# motor_control.net
KiCad netlist of a schematic drawn in EAGLE
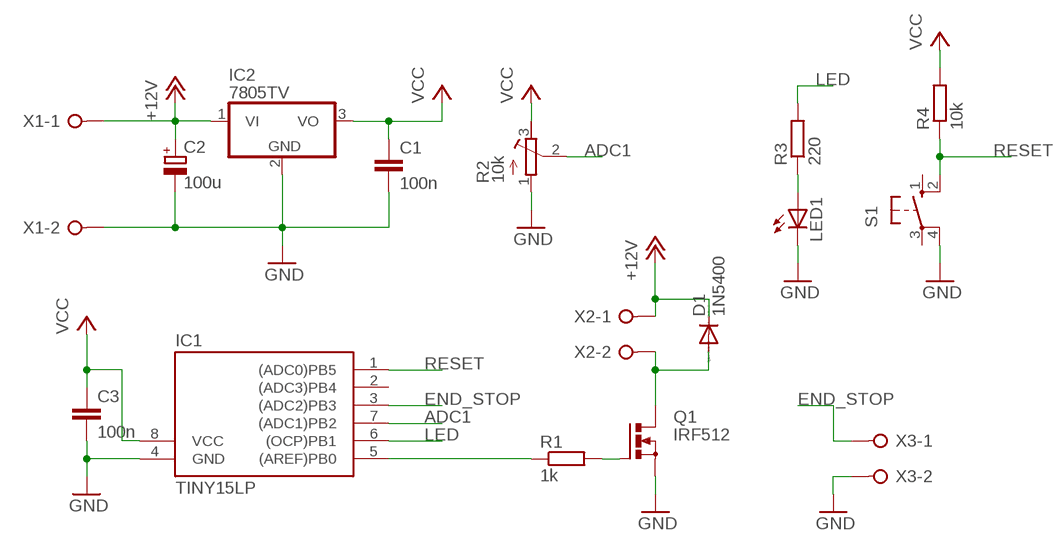
[diagram p0: schematic, sheet 1]

(export (version "E")
  (design (tool "Eeschema 10.0.6"))
  (components
    (comp (ref "C1")
      (value "100n")
      (footprint "eagle-import:C025-025X050")
      (libsource (lib "eagle-import") (part "C-EU025-025X050"))
    )
    (comp (ref "C2")
      (value "100u")
      (footprint "eagle-import:E2,5-6E")
      (libsource (lib "eagle-import") (part "CPOL-EUE2,5-6E"))
    )
    (comp (ref "C3")
      (value "100n")
      (footprint "eagle-import:C025-025X050")
      (libsource (lib "eagle-import") (part "C-EU025-025X050"))
    )
    (comp (ref "D1")
      (value "1N5400")
      (footprint "eagle-import:DO201-15")
      (libsource (lib "eagle-import") (part "1N5400"))
    )
    (comp (ref "IC1")
      (value "TINY15LP")
      (footprint "eagle-import:DIL08")
      (libsource (lib "eagle-import") (part "TINY15LP"))
    )
    (comp (ref "IC2")
      (value "7805TV")
      (footprint "eagle-import:TO220V")
      (libsource (lib "eagle-import") (part "78TV05"))
    )
    (comp (ref "LED1")
      (value "LED5MM")
      (footprint "eagle-import:LED5MM")
      (libsource (lib "eagle-import") (part "LED5MM"))
    )
    (comp (ref "Q1")
      (value "IRF512")
      (footprint "eagle-import:TO220BV")
      (libsource (lib "eagle-import") (part "IRF512"))
    )
    (comp (ref "R1")
      (value "1k")
      (footprint "eagle-import:0309_10")
      (libsource (lib "eagle-import") (part "R-EU_0309/10"))
    )
    (comp (ref "R2")
      (value "10k")
      (footprint "eagle-import:RTRIM3296W")
      (libsource (lib "eagle-import") (part "R-TRIMM3296W"))
    )
    (comp (ref "R3")
      (value "220")
      (footprint "eagle-import:0309_10")
      (libsource (lib "eagle-import") (part "R-EU_0309/10"))
    )
    (comp (ref "R4")
      (value "10k")
      (footprint "eagle-import:0309_10")
      (libsource (lib "eagle-import") (part "R-EU_0309/10"))
    )
    (comp (ref "S1")
      (value "40-XX")
      (footprint "eagle-import:B3F-40XX")
      (fields (field (name "MF") "OMRON COMPONENTS USA") (field (name "MPN") "B3F-4000"))
      (libsource (lib "eagle-import") (part "40-XX"))
    )
    (comp (ref "X1")
      (value "W237-02P")
      (footprint "eagle-import:W237-132")
      (libsource (lib "eagle-import") (part "W237-02P"))
    )
    (comp (ref "X2")
      (value "W237-02P")
      (footprint "eagle-import:W237-132")
      (libsource (lib "eagle-import") (part "W237-02P"))
    )
    (comp (ref "X3")
      (value "W237-02P")
      (footprint "eagle-import:W237-132")
      (libsource (lib "eagle-import") (part "W237-02P"))
    )
  )
  (nets
    (net (code "1") (name "+12V") (class "Default")
      (node (ref "C2") (pin "+") (pinfunction "+_+") (pintype "passive"))
      (node (ref "D1") (pin "C") (pinfunction "C_C") (pintype "passive"))
      (node (ref "IC2") (pin "1") (pinfunction "VI_1") (pintype "input"))
      (node (ref "X1") (pin "1") (pinfunction "KL_1") (pintype "passive"))
      (node (ref "X2") (pin "1") (pinfunction "KL_1") (pintype "passive"))
    )
    (net (code "2") (name "/ADC1") (class "Default")
      (node (ref "IC1") (pin "7") (pinfunction "(ADC1)PB2_7") (pintype "bidirectional"))
      (node (ref "R2") (pin "2") (pinfunction "S_2") (pintype "passive"))
    )
    (net (code "3") (name "/END_STOP") (class "Default")
      (node (ref "IC1") (pin "3") (pinfunction "(ADC2)PB3_3") (pintype "bidirectional"))
      (node (ref "X3") (pin "1") (pinfunction "KL_1") (pintype "passive"))
    )
    (net (code "4") (name "/LED") (class "Default")
      (node (ref "IC1") (pin "6") (pinfunction "(OCP)PB1_6") (pintype "bidirectional"))
      (node (ref "R3") (pin "2") (pinfunction "2_2") (pintype "passive"))
    )
    (net (code "5") (name "/RESET") (class "Default")
      (node (ref "IC1") (pin "1") (pinfunction "(ADC0)PB5_1") (pintype "bidirectional"))
      (node (ref "R4") (pin "1") (pinfunction "1_1") (pintype "passive"))
      (node (ref "S1") (pin "2") (pinfunction "S1_2") (pintype "passive"))
    )
    (net (code "6") (name "GND") (class "Default")
      (node (ref "C1") (pin "2") (pinfunction "2_2") (pintype "passive"))
      (node (ref "C2") (pin "-") (pinfunction "-_-") (pintype "passive"))
      (node (ref "C3") (pin "2") (pinfunction "2_2") (pintype "passive"))
      (node (ref "IC1") (pin "4") (pinfunction "GND_4") (pintype "power_in"))
      (node (ref "IC2") (pin "2") (pinfunction "GND_2") (pintype "passive"))
      (node (ref "LED1") (pin "K") (pinfunction "C_K") (pintype "passive"))
      (node (ref "Q1") (pin "S") (pinfunction "S_S") (pintype "passive"))
      (node (ref "R2") (pin "1") (pinfunction "A_1") (pintype "passive"))
      (node (ref "S1") (pin "4") (pinfunction "P1_4") (pintype "passive"))
      (node (ref "X1") (pin "2") (pinfunction "KL_2") (pintype "passive"))
      (node (ref "X3") (pin "2") (pinfunction "KL_2") (pintype "passive"))
    )
    (net (code "7") (name "Net-(IC1-(AREF)PB0)") (class "Default")
      (node (ref "IC1") (pin "5") (pinfunction "(AREF)PB0_5") (pintype "bidirectional"))
      (node (ref "R1") (pin "1") (pinfunction "1_1") (pintype "passive"))
    )
    (net (code "8") (name "Net-(LED1-PadA)") (class "Default")
      (node (ref "LED1") (pin "A") (pinfunction "A_A") (pintype "passive"))
      (node (ref "R3") (pin "1") (pinfunction "1_1") (pintype "passive"))
    )
    (net (code "9") (name "Net-(Q1-PadG)") (class "Default")
      (node (ref "Q1") (pin "G") (pinfunction "G_G") (pintype "passive"))
      (node (ref "R1") (pin "2") (pinfunction "2_2") (pintype "passive"))
    )
    (net (code "10") (name "Net-(X2B-KL)") (class "Default")
      (node (ref "D1") (pin "A") (pinfunction "A_A") (pintype "passive"))
      (node (ref "Q1") (pin "D") (pinfunction "D_D") (pintype "passive"))
      (node (ref "X2") (pin "2") (pinfunction "KL_2") (pintype "passive"))
    )
    (net (code "11") (name "VCC") (class "Default")
      (node (ref "C1") (pin "1") (pinfunction "1_1") (pintype "passive"))
      (node (ref "C3") (pin "1") (pinfunction "1_1") (pintype "passive"))
      (node (ref "IC1") (pin "8") (pinfunction "VCC_8") (pintype "power_in"))
      (node (ref "IC2") (pin "3") (pinfunction "VO_3") (pintype "passive"))
      (node (ref "R2") (pin "3") (pinfunction "E_3") (pintype "passive"))
      (node (ref "R4") (pin "2") (pinfunction "2_2") (pintype "passive"))
    )
    (net (code "12") (name "unconnected-(IC1-(ADC3)PB4-Pad2)") (class "Default")
      (node (ref "IC1") (pin "2") (pinfunction "(ADC3)PB4_2") (pintype "bidirectional"))
    )
    (net (code "13") (name "unconnected-(S1-P-Pad3)") (class "Default")
      (node (ref "S1") (pin "3") (pinfunction "P_3") (pintype "passive"))
    )
    (net (code "14") (name "unconnected-(S1-S-Pad1)") (class "Default")
      (node (ref "S1") (pin "1") (pinfunction "S_1") (pintype "passive"))
    )
  )
)
